# Dual_Motor_Driver.net
KiCad netlist of a schematic drawn in EAGLE
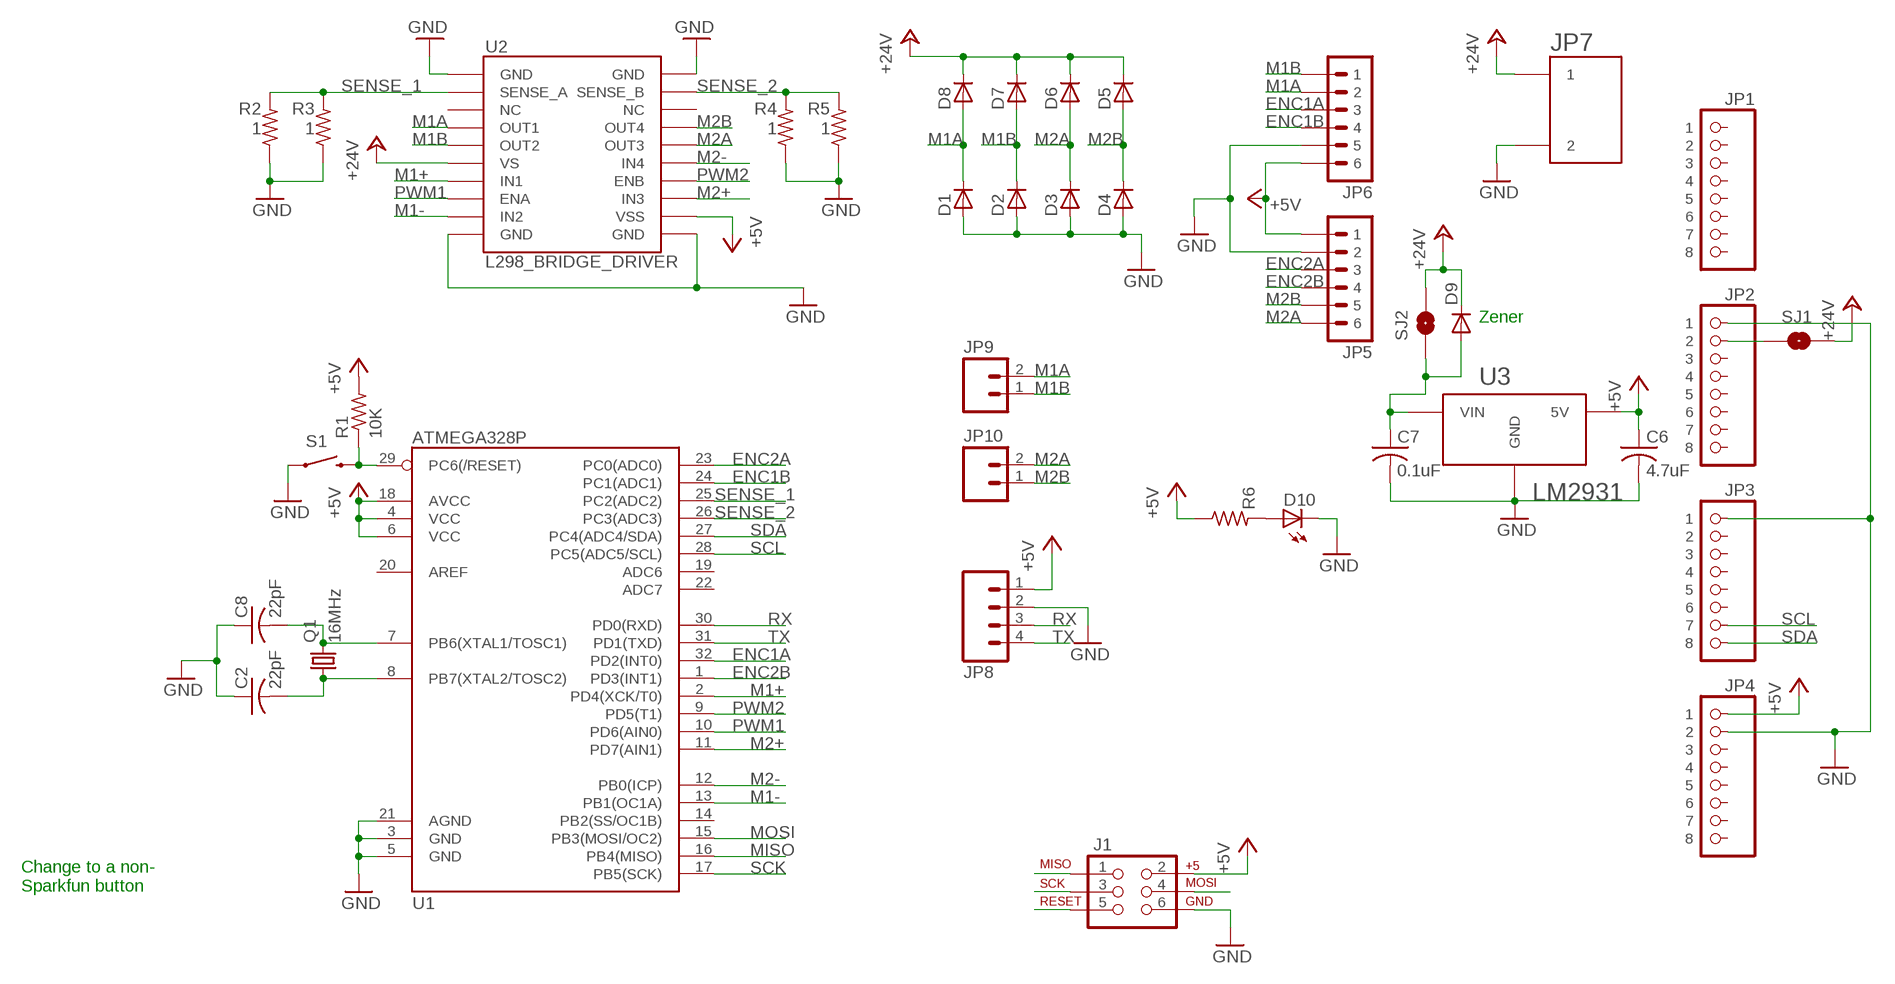
[diagram p0: schematic, sheet 1]

(export (version "E")
  (design (tool "Eeschema 10.0.6"))
  (components
    (comp (ref "C2")
      (value "22pF")
      (footprint "eagle-import:C0603")
      (libsource (lib "eagle-import") (part "C-USC0603"))
    )
    (comp (ref "C6")
      (value "4.7uF")
      (footprint "eagle-import:C0603")
      (libsource (lib "eagle-import") (part "C-USC0603"))
    )
    (comp (ref "C7")
      (value "0.1uF")
      (footprint "eagle-import:C0603")
      (libsource (lib "eagle-import") (part "C-USC0603"))
    )
    (comp (ref "C8")
      (value "22pF")
      (footprint "eagle-import:C0603")
      (libsource (lib "eagle-import") (part "C-USC0603"))
    )
    (comp (ref "D1")
      (value "D-SOD123")
      (footprint "eagle-import:SOD123")
      (fields (field (name "PART#") "CDBW140-G"))
      (libsource (lib "eagle-import") (part "D-SOD123"))
    )
    (comp (ref "D2")
      (value "D-SOD123")
      (footprint "eagle-import:SOD123")
      (fields (field (name "PART#") "CDBW140-G"))
      (libsource (lib "eagle-import") (part "D-SOD123"))
    )
    (comp (ref "D3")
      (value "D-SOD123")
      (footprint "eagle-import:SOD123")
      (fields (field (name "PART#") "CDBW140-G"))
      (libsource (lib "eagle-import") (part "D-SOD123"))
    )
    (comp (ref "D4")
      (value "D-SOD123")
      (footprint "eagle-import:SOD123")
      (fields (field (name "PART#") "CDBW140-G"))
      (libsource (lib "eagle-import") (part "D-SOD123"))
    )
    (comp (ref "D5")
      (value "D-SOD123")
      (footprint "eagle-import:SOD123")
      (fields (field (name "PART#") "CDBW140-G"))
      (libsource (lib "eagle-import") (part "D-SOD123"))
    )
    (comp (ref "D6")
      (value "D-SOD123")
      (footprint "eagle-import:SOD123")
      (fields (field (name "PART#") "CDBW140-G"))
      (libsource (lib "eagle-import") (part "D-SOD123"))
    )
    (comp (ref "D7")
      (value "D-SOD123")
      (footprint "eagle-import:SOD123")
      (fields (field (name "PART#") "CDBW140-G"))
      (libsource (lib "eagle-import") (part "D-SOD123"))
    )
    (comp (ref "D8")
      (value "D-SOD123")
      (footprint "eagle-import:SOD123")
      (fields (field (name "PART#") "CDBW140-G"))
      (libsource (lib "eagle-import") (part "D-SOD123"))
    )
    (comp (ref "D9")
      (value "DIODE-DO214AA")
      (footprint "eagle-import:DO214AA")
      (libsource (lib "eagle-import") (part "DIODE-DO214AA"))
    )
    (comp (ref "D10")
      (value "LED-GREENLED-0805_NO_SILK")
      (footprint "eagle-import:LED-0805")
      (libsource (lib "eagle-import") (part "LED-GREENLED-0805_NO_SILK"))
    )
    (comp (ref "J1")
      (value "AVR_SPI_PRG_62X3_LOCK")
      (footprint "eagle-import:2X3_LOCK")
      (libsource (lib "eagle-import") (part "AVR_SPI_PRG_62X3_LOCK"))
    )
    (comp (ref "JP1")
      (value "8-PIN_HEADER")
      (footprint "eagle-import:8-PIN_RECEPTACLE_LOCK_NO-SS")
      (libsource (lib "eagle-import") (part "8-PIN_HEADER"))
    )
    (comp (ref "JP2")
      (value "8-PIN_HEADER")
      (footprint "eagle-import:8-PIN_RECEPTACLE_LOCK_NO-SS")
      (libsource (lib "eagle-import") (part "8-PIN_HEADER"))
    )
    (comp (ref "JP3")
      (value "8-PIN_HEADER")
      (footprint "eagle-import:8-PIN_RECEPTACLE_LOCK_NO-SS")
      (libsource (lib "eagle-import") (part "8-PIN_HEADER"))
    )
    (comp (ref "JP4")
      (value "8-PIN_HEADER")
      (footprint "eagle-import:8-PIN_RECEPTACLE_LOCK_NO-SS")
      (libsource (lib "eagle-import") (part "8-PIN_HEADER"))
    )
    (comp (ref "JP5")
      (value "6PIN-SH_RIGHT_ANGLE")
      (footprint "eagle-import:6PIN-SH_SERIES_RA")
      (fields (field (name "PART#") "SM06B-SRSS-TB(LF)(SN)"))
      (libsource (lib "eagle-import") (part "6PIN-SH_RIGHT_ANGLE"))
    )
    (comp (ref "JP6")
      (value "6PIN-SH_RIGHT_ANGLE")
      (footprint "eagle-import:6PIN-SH_SERIES_RA")
      (fields (field (name "PART#") "SM06B-SRSS-TB(LF)(SN)"))
      (libsource (lib "eagle-import") (part "6PIN-SH_RIGHT_ANGLE"))
    )
    (comp (ref "JP7")
      (value "2-POS_SMD_TERM_BLOCK")
      (footprint "eagle-import:2-POS_SMD_TERMINAL_BLOCK")
      (libsource (lib "eagle-import") (part "2-POS_SMD_TERM_BLOCK"))
    )
    (comp (ref "JP8")
      (value "M04LOCK")
      (footprint "eagle-import:1X04_LOCK")
      (libsource (lib "eagle-import") (part "M04LOCK"))
    )
    (comp (ref "JP9")
      (value "M02PTH")
      (footprint "eagle-import:1X02")
      (libsource (lib "eagle-import") (part "M02PTH"))
    )
    (comp (ref "JP10")
      (value "M02PTH")
      (footprint "eagle-import:1X02")
      (libsource (lib "eagle-import") (part "M02PTH"))
    )
    (comp (ref "Q1")
      (value "16MHz")
      (footprint "eagle-import:CTS406")
      (fields (field (name "PART#") "406C35D16M00000"))
      (libsource (lib "eagle-import") (part "CRYSTALCTS406"))
    )
    (comp (ref "R1")
      (value "10K")
      (footprint "eagle-import:R0603")
      (libsource (lib "eagle-import") (part "R-US_R0603"))
    )
    (comp (ref "R2")
      (value "1")
      (footprint "eagle-import:R0603")
      (libsource (lib "eagle-import") (part "R-US_R0603"))
    )
    (comp (ref "R3")
      (value "1")
      (footprint "eagle-import:R0603")
      (libsource (lib "eagle-import") (part "R-US_R0603"))
    )
    (comp (ref "R4")
      (value "1")
      (footprint "eagle-import:R0603")
      (libsource (lib "eagle-import") (part "R-US_R0603"))
    )
    (comp (ref "R5")
      (value "1")
      (footprint "eagle-import:R0603")
      (libsource (lib "eagle-import") (part "R-US_R0603"))
    )
    (comp (ref "R6")
      (value "R-US_R0603")
      (footprint "eagle-import:R0603")
      (libsource (lib "eagle-import") (part "R-US_R0603"))
    )
    (comp (ref "S1")
      (value "SWITCH-MOMENTARY-2SMD")
      (footprint "eagle-import:TACTILE_SWITCH_SMD")
      (libsource (lib "eagle-import") (part "SWITCH-MOMENTARY-2SMD"))
    )
    (comp (ref "SJ1")
      (value "SOLDERJUMPERNC")
      (footprint "eagle-import:SJ_2S")
      (libsource (lib "eagle-import") (part "SOLDERJUMPERNC"))
    )
    (comp (ref "SJ2")
      (value "SOLDERJUMPERTRACE")
      (footprint "eagle-import:SJ_2S-TRACE")
      (libsource (lib "eagle-import") (part "SOLDERJUMPERTRACE"))
    )
    (comp (ref "U1")
      (value "ATMEGA328P")
      (footprint "eagle-import:TQFP32-08")
      (libsource (lib "eagle-import") (part "ATMEGA328_SMT"))
    )
    (comp (ref "U2")
      (value "L298_BRIDGE_DRIVER")
      (footprint "eagle-import:POWERSO20")
      (libsource (lib "eagle-import") (part "L298_BRIDGE_DRIVER"))
    )
    (comp (ref "U3")
      (value "LM2931")
      (footprint "eagle-import:TO263")
      (libsource (lib "eagle-import") (part "LM2931"))
    )
  )
  (nets
    (net (code "1") (name "+5V") (class "Default")
      (node (ref "C6") (pin "1") (pinfunction "1_1") (pintype "passive"))
      (node (ref "J1") (pin "2") (pinfunction "2_2") (pintype "passive"))
      (node (ref "JP4") (pin "P$1") (pinfunction "1_P$1") (pintype "passive"))
      (node (ref "JP5") (pin "P$1") (pinfunction "1_P$1") (pintype "passive"))
      (node (ref "JP6") (pin "P$6") (pinfunction "6_P$6") (pintype "passive"))
      (node (ref "JP8") (pin "1") (pinfunction "1_1") (pintype "passive"))
      (node (ref "R1") (pin "2") (pinfunction "2_2") (pintype "passive"))
      (node (ref "R6") (pin "1") (pinfunction "1_1") (pintype "passive"))
      (node (ref "U1") (pin "18") (pinfunction "AVCC_18") (pintype "bidirectional"))
      (node (ref "U1") (pin "4") (pinfunction "VCC_4") (pintype "bidirectional"))
      (node (ref "U1") (pin "6") (pinfunction "VCC_6") (pintype "bidirectional"))
      (node (ref "U2") (pin "12") (pinfunction "VSS_12") (pintype "bidirectional"))
      (node (ref "U3") (pin "P$3") (pinfunction "5V_P$3") (pintype "bidirectional"))
    )
    (net (code "2") (name "+24V") (class "Default")
      (node (ref "D5") (pin "1") (pinfunction "C_1") (pintype "passive"))
      (node (ref "D6") (pin "1") (pinfunction "C_1") (pintype "passive"))
      (node (ref "D7") (pin "1") (pinfunction "C_1") (pintype "passive"))
      (node (ref "D8") (pin "1") (pinfunction "C_1") (pintype "passive"))
      (node (ref "D9") (pin "C") (pinfunction "C_C") (pintype "passive"))
      (node (ref "JP7") (pin "P$3") (pinfunction "1_P$3") (pintype "bidirectional"))
      (node (ref "SJ1") (pin "2") (pinfunction "2_2") (pintype "passive"))
      (node (ref "SJ2") (pin "2") (pinfunction "2_2") (pintype "passive"))
      (node (ref "U2") (pin "6") (pinfunction "VS_6") (pintype "bidirectional"))
    )
    (net (code "3") (name "/ENC1A") (class "Default")
      (node (ref "JP6") (pin "P$3") (pinfunction "3_P$3") (pintype "passive"))
      (node (ref "U1") (pin "32") (pinfunction "PD2(INT0)_32") (pintype "bidirectional"))
    )
    (net (code "4") (name "/ENC1B") (class "Default")
      (node (ref "JP6") (pin "P$4") (pinfunction "4_P$4") (pintype "passive"))
      (node (ref "U1") (pin "24") (pinfunction "PC1(ADC1)_24") (pintype "bidirectional"))
    )
    (net (code "5") (name "/ENC2A") (class "Default")
      (node (ref "JP5") (pin "P$3") (pinfunction "3_P$3") (pintype "passive"))
      (node (ref "U1") (pin "23") (pinfunction "PC0(ADC0)_23") (pintype "bidirectional"))
    )
    (net (code "6") (name "/ENC2B") (class "Default")
      (node (ref "JP5") (pin "P$4") (pinfunction "4_P$4") (pintype "passive"))
      (node (ref "U1") (pin "1") (pinfunction "PD3(INT1)_1") (pintype "bidirectional"))
    )
    (net (code "7") (name "/M1+") (class "Default")
      (node (ref "U1") (pin "2") (pinfunction "PD4(XCK/T0)_2") (pintype "bidirectional"))
      (node (ref "U2") (pin "7") (pinfunction "IN1_7") (pintype "bidirectional"))
    )
    (net (code "8") (name "/M1-") (class "Default")
      (node (ref "U1") (pin "13") (pinfunction "PB1(OC1A)_13") (pintype "bidirectional"))
      (node (ref "U2") (pin "9") (pinfunction "IN2_9") (pintype "bidirectional"))
    )
    (net (code "9") (name "/M1A") (class "Default")
      (node (ref "D1") (pin "1") (pinfunction "C_1") (pintype "passive"))
      (node (ref "D8") (pin "2") (pinfunction "A_2") (pintype "passive"))
      (node (ref "JP6") (pin "P$2") (pinfunction "2_P$2") (pintype "passive"))
      (node (ref "JP9") (pin "2") (pinfunction "2_2") (pintype "passive"))
      (node (ref "U2") (pin "4") (pinfunction "OUT1_4") (pintype "bidirectional"))
    )
    (net (code "10") (name "/M1B") (class "Default")
      (node (ref "D2") (pin "1") (pinfunction "C_1") (pintype "passive"))
      (node (ref "D7") (pin "2") (pinfunction "A_2") (pintype "passive"))
      (node (ref "JP6") (pin "P$1") (pinfunction "1_P$1") (pintype "passive"))
      (node (ref "JP9") (pin "1") (pinfunction "1_1") (pintype "passive"))
      (node (ref "U2") (pin "5") (pinfunction "OUT2_5") (pintype "bidirectional"))
    )
    (net (code "11") (name "/M2+") (class "Default")
      (node (ref "U1") (pin "11") (pinfunction "PD7(AIN1)_11") (pintype "bidirectional"))
      (node (ref "U2") (pin "13") (pinfunction "IN3_13") (pintype "bidirectional"))
    )
    (net (code "12") (name "/M2-") (class "Default")
      (node (ref "U1") (pin "12") (pinfunction "PB0(ICP)_12") (pintype "bidirectional"))
      (node (ref "U2") (pin "15") (pinfunction "IN4_15") (pintype "bidirectional"))
    )
    (net (code "13") (name "/M2A") (class "Default")
      (node (ref "D3") (pin "1") (pinfunction "C_1") (pintype "passive"))
      (node (ref "D6") (pin "2") (pinfunction "A_2") (pintype "passive"))
      (node (ref "JP10") (pin "2") (pinfunction "2_2") (pintype "passive"))
      (node (ref "JP5") (pin "P$6") (pinfunction "6_P$6") (pintype "passive"))
      (node (ref "U2") (pin "16") (pinfunction "OUT3_16") (pintype "bidirectional"))
    )
    (net (code "14") (name "/M2B") (class "Default")
      (node (ref "D4") (pin "1") (pinfunction "C_1") (pintype "passive"))
      (node (ref "D5") (pin "2") (pinfunction "A_2") (pintype "passive"))
      (node (ref "JP10") (pin "1") (pinfunction "1_1") (pintype "passive"))
      (node (ref "JP5") (pin "P$5") (pinfunction "5_P$5") (pintype "passive"))
      (node (ref "U2") (pin "17") (pinfunction "OUT4_17") (pintype "bidirectional"))
    )
    (net (code "15") (name "/MISO") (class "Default")
      (node (ref "J1") (pin "1") (pinfunction "1_1") (pintype "passive"))
      (node (ref "U1") (pin "16") (pinfunction "PB4(MISO)_16") (pintype "bidirectional"))
    )
    (net (code "16") (name "/MOSI") (class "Default")
      (node (ref "J1") (pin "4") (pinfunction "4_4") (pintype "passive"))
      (node (ref "U1") (pin "15") (pinfunction "PB3(MOSI/OC2)_15") (pintype "bidirectional"))
    )
    (net (code "17") (name "/PWM1") (class "Default")
      (node (ref "U1") (pin "10") (pinfunction "PD6(AIN0)_10") (pintype "bidirectional"))
      (node (ref "U2") (pin "8") (pinfunction "ENA_8") (pintype "bidirectional"))
    )
    (net (code "18") (name "/PWM2") (class "Default")
      (node (ref "U1") (pin "9") (pinfunction "PD5(T1)_9") (pintype "bidirectional"))
      (node (ref "U2") (pin "14") (pinfunction "ENB_14") (pintype "bidirectional"))
    )
    (net (code "19") (name "/RESET") (class "Default")
      (node (ref "J1") (pin "5") (pinfunction "5_5") (pintype "passive"))
      (node (ref "R1") (pin "1") (pinfunction "1_1") (pintype "passive"))
      (node (ref "S1") (pin "3") (pinfunction "2_3") (pintype "passive"))
      (node (ref "U1") (pin "29") (pinfunction "PC6(/RESET)_29") (pintype "bidirectional"))
    )
    (net (code "20") (name "/RX") (class "Default")
      (node (ref "JP8") (pin "3") (pinfunction "3_3") (pintype "passive"))
      (node (ref "U1") (pin "30") (pinfunction "PD0(RXD)_30") (pintype "bidirectional"))
    )
    (net (code "21") (name "/SCK") (class "Default")
      (node (ref "J1") (pin "3") (pinfunction "3_3") (pintype "passive"))
      (node (ref "U1") (pin "17") (pinfunction "PB5(SCK)_17") (pintype "bidirectional"))
    )
    (net (code "22") (name "/SCL") (class "Default")
      (node (ref "JP3") (pin "P$7") (pinfunction "7_P$7") (pintype "passive"))
      (node (ref "U1") (pin "28") (pinfunction "PC5(ADC5/SCL)_28") (pintype "bidirectional"))
    )
    (net (code "23") (name "/SDA") (class "Default")
      (node (ref "JP3") (pin "P$8") (pinfunction "8_P$8") (pintype "passive"))
      (node (ref "U1") (pin "27") (pinfunction "PC4(ADC4/SDA)_27") (pintype "bidirectional"))
    )
    (net (code "24") (name "/SENSE_1") (class "Default")
      (node (ref "R2") (pin "2") (pinfunction "2_2") (pintype "passive"))
      (node (ref "R3") (pin "2") (pinfunction "2_2") (pintype "passive"))
      (node (ref "U1") (pin "25") (pinfunction "PC2(ADC2)_25") (pintype "bidirectional"))
      (node (ref "U2") (pin "2") (pinfunction "SENSE_A_2") (pintype "bidirectional"))
    )
    (net (code "25") (name "/SENSE_2") (class "Default")
      (node (ref "R4") (pin "2") (pinfunction "2_2") (pintype "passive"))
      (node (ref "R5") (pin "2") (pinfunction "2_2") (pintype "passive"))
      (node (ref "U1") (pin "26") (pinfunction "PC3(ADC3)_26") (pintype "bidirectional"))
      (node (ref "U2") (pin "19") (pinfunction "SENSE_B_19") (pintype "bidirectional"))
    )
    (net (code "26") (name "/TX") (class "Default")
      (node (ref "JP8") (pin "4") (pinfunction "4_4") (pintype "passive"))
      (node (ref "U1") (pin "31") (pinfunction "PD1(TXD)_31") (pintype "bidirectional"))
    )
    (net (code "27") (name "GND") (class "Default")
      (node (ref "C2") (pin "1") (pinfunction "1_1") (pintype "passive"))
      (node (ref "C6") (pin "2") (pinfunction "2_2") (pintype "passive"))
      (node (ref "C7") (pin "2") (pinfunction "2_2") (pintype "passive"))
      (node (ref "C8") (pin "1") (pinfunction "1_1") (pintype "passive"))
      (node (ref "D1") (pin "2") (pinfunction "A_2") (pintype "passive"))
      (node (ref "D10") (pin "2") (pinfunction "C_2") (pintype "passive"))
      (node (ref "D2") (pin "2") (pinfunction "A_2") (pintype "passive"))
      (node (ref "D3") (pin "2") (pinfunction "A_2") (pintype "passive"))
      (node (ref "D4") (pin "2") (pinfunction "A_2") (pintype "passive"))
      (node (ref "J1") (pin "6") (pinfunction "6_6") (pintype "passive"))
      (node (ref "JP2") (pin "P$1") (pinfunction "1_P$1") (pintype "passive"))
      (node (ref "JP3") (pin "P$1") (pinfunction "1_P$1") (pintype "passive"))
      (node (ref "JP4") (pin "P$2") (pinfunction "2_P$2") (pintype "passive"))
      (node (ref "JP5") (pin "P$2") (pinfunction "2_P$2") (pintype "passive"))
      (node (ref "JP6") (pin "P$5") (pinfunction "5_P$5") (pintype "passive"))
      (node (ref "JP7") (pin "P$4") (pinfunction "2_P$4") (pintype "bidirectional"))
      (node (ref "JP8") (pin "2") (pinfunction "2_2") (pintype "passive"))
      (node (ref "R2") (pin "1") (pinfunction "1_1") (pintype "passive"))
      (node (ref "R3") (pin "1") (pinfunction "1_1") (pintype "passive"))
      (node (ref "R4") (pin "1") (pinfunction "1_1") (pintype "passive"))
      (node (ref "R5") (pin "1") (pinfunction "1_1") (pintype "passive"))
      (node (ref "S1") (pin "1") (pinfunction "1_1") (pintype "passive"))
      (node (ref "U1") (pin "21") (pinfunction "AGND_21") (pintype "bidirectional"))
      (node (ref "U1") (pin "3") (pinfunction "GND_3") (pintype "bidirectional"))
      (node (ref "U1") (pin "5") (pinfunction "GND_5") (pintype "bidirectional"))
      (node (ref "U2") (pin "1") (pinfunction "GND_1") (pintype "bidirectional"))
      (node (ref "U2") (pin "10") (pinfunction "GND_10") (pintype "bidirectional"))
      (node (ref "U2") (pin "11") (pinfunction "GND_11") (pintype "bidirectional"))
      (node (ref "U2") (pin "20") (pinfunction "GND_20") (pintype "bidirectional"))
      (node (ref "U3") (pin "P$1") (pinfunction "GND_P$1") (pintype "bidirectional"))
    )
    (net (code "28") (name "Net-(D10-A)") (class "Default")
      (node (ref "D10") (pin "1") (pinfunction "A_1") (pintype "passive"))
      (node (ref "R6") (pin "2") (pinfunction "2_2") (pintype "passive"))
    )
    (net (code "29") (name "Net-(JP2-2)") (class "Default")
      (node (ref "JP2") (pin "P$2") (pinfunction "2_P$2") (pintype "passive"))
      (node (ref "SJ1") (pin "1") (pinfunction "1_1") (pintype "passive"))
    )
    (net (code "30") (name "Net-(Q1-2)") (class "Default")
      (node (ref "C8") (pin "2") (pinfunction "2_2") (pintype "passive"))
      (node (ref "Q1") (pin "3") (pinfunction "2_3") (pintype "passive"))
      (node (ref "U1") (pin "7") (pinfunction "PB6(XTAL1/TOSC1)_7") (pintype "bidirectional"))
    )
    (net (code "31") (name "Net-(U1-PB7(XTAL2{slash}TOSC2))") (class "Default")
      (node (ref "C2") (pin "2") (pinfunction "2_2") (pintype "passive"))
      (node (ref "Q1") (pin "1") (pinfunction "1_1") (pintype "passive"))
      (node (ref "U1") (pin "8") (pinfunction "PB7(XTAL2/TOSC2)_8") (pintype "bidirectional"))
    )
    (net (code "32") (name "Net-(U3-VIN)") (class "Default")
      (node (ref "C7") (pin "1") (pinfunction "1_1") (pintype "passive"))
      (node (ref "D9") (pin "A") (pinfunction "A_A") (pintype "passive"))
      (node (ref "SJ2") (pin "1") (pinfunction "1_1") (pintype "passive"))
      (node (ref "U3") (pin "P$2") (pinfunction "VIN_P$2") (pintype "bidirectional"))
    )
    (net (code "33") (name "unconnected-(JP1-1-PadP$1)") (class "Default")
      (node (ref "JP1") (pin "P$1") (pinfunction "1_P$1") (pintype "passive"))
    )
    (net (code "34") (name "unconnected-(JP1-2-PadP$2)") (class "Default")
      (node (ref "JP1") (pin "P$2") (pinfunction "2_P$2") (pintype "passive"))
    )
    (net (code "35") (name "unconnected-(JP1-3-PadP$3)") (class "Default")
      (node (ref "JP1") (pin "P$3") (pinfunction "3_P$3") (pintype "passive"))
    )
    (net (code "36") (name "unconnected-(JP1-4-PadP$4)") (class "Default")
      (node (ref "JP1") (pin "P$4") (pinfunction "4_P$4") (pintype "passive"))
    )
    (net (code "37") (name "unconnected-(JP1-5-PadP$5)") (class "Default")
      (node (ref "JP1") (pin "P$5") (pinfunction "5_P$5") (pintype "passive"))
    )
    (net (code "38") (name "unconnected-(JP1-6-PadP$6)") (class "Default")
      (node (ref "JP1") (pin "P$6") (pinfunction "6_P$6") (pintype "passive"))
    )
    (net (code "39") (name "unconnected-(JP1-7-PadP$7)") (class "Default")
      (node (ref "JP1") (pin "P$7") (pinfunction "7_P$7") (pintype "passive"))
    )
    (net (code "40") (name "unconnected-(JP1-8-PadP$8)") (class "Default")
      (node (ref "JP1") (pin "P$8") (pinfunction "8_P$8") (pintype "passive"))
    )
    (net (code "41") (name "unconnected-(JP2-3-PadP$3)") (class "Default")
      (node (ref "JP2") (pin "P$3") (pinfunction "3_P$3") (pintype "passive"))
    )
    (net (code "42") (name "unconnected-(JP2-4-PadP$4)") (class "Default")
      (node (ref "JP2") (pin "P$4") (pinfunction "4_P$4") (pintype "passive"))
    )
    (net (code "43") (name "unconnected-(JP2-5-PadP$5)") (class "Default")
      (node (ref "JP2") (pin "P$5") (pinfunction "5_P$5") (pintype "passive"))
    )
    (net (code "44") (name "unconnected-(JP2-6-PadP$6)") (class "Default")
      (node (ref "JP2") (pin "P$6") (pinfunction "6_P$6") (pintype "passive"))
    )
    (net (code "45") (name "unconnected-(JP2-7-PadP$7)") (class "Default")
      (node (ref "JP2") (pin "P$7") (pinfunction "7_P$7") (pintype "passive"))
    )
    (net (code "46") (name "unconnected-(JP2-8-PadP$8)") (class "Default")
      (node (ref "JP2") (pin "P$8") (pinfunction "8_P$8") (pintype "passive"))
    )
    (net (code "47") (name "unconnected-(JP3-2-PadP$2)") (class "Default")
      (node (ref "JP3") (pin "P$2") (pinfunction "2_P$2") (pintype "passive"))
    )
    (net (code "48") (name "unconnected-(JP3-3-PadP$3)") (class "Default")
      (node (ref "JP3") (pin "P$3") (pinfunction "3_P$3") (pintype "passive"))
    )
    (net (code "49") (name "unconnected-(JP3-4-PadP$4)") (class "Default")
      (node (ref "JP3") (pin "P$4") (pinfunction "4_P$4") (pintype "passive"))
    )
    (net (code "50") (name "unconnected-(JP3-5-PadP$5)") (class "Default")
      (node (ref "JP3") (pin "P$5") (pinfunction "5_P$5") (pintype "passive"))
    )
    (net (code "51") (name "unconnected-(JP3-6-PadP$6)") (class "Default")
      (node (ref "JP3") (pin "P$6") (pinfunction "6_P$6") (pintype "passive"))
    )
    (net (code "52") (name "unconnected-(JP4-3-PadP$3)") (class "Default")
      (node (ref "JP4") (pin "P$3") (pinfunction "3_P$3") (pintype "passive"))
    )
    (net (code "53") (name "unconnected-(JP4-4-PadP$4)") (class "Default")
      (node (ref "JP4") (pin "P$4") (pinfunction "4_P$4") (pintype "passive"))
    )
    (net (code "54") (name "unconnected-(JP4-5-PadP$5)") (class "Default")
      (node (ref "JP4") (pin "P$5") (pinfunction "5_P$5") (pintype "passive"))
    )
    (net (code "55") (name "unconnected-(JP4-6-PadP$6)") (class "Default")
      (node (ref "JP4") (pin "P$6") (pinfunction "6_P$6") (pintype "passive"))
    )
    (net (code "56") (name "unconnected-(JP4-7-PadP$7)") (class "Default")
      (node (ref "JP4") (pin "P$7") (pinfunction "7_P$7") (pintype "passive"))
    )
    (net (code "57") (name "unconnected-(JP4-8-PadP$8)") (class "Default")
      (node (ref "JP4") (pin "P$8") (pinfunction "8_P$8") (pintype "passive"))
    )
    (net (code "58") (name "unconnected-(U1-ADC6-Pad19)") (class "Default")
      (node (ref "U1") (pin "19") (pinfunction "ADC6_19") (pintype "bidirectional"))
    )
    (net (code "59") (name "unconnected-(U1-ADC7-Pad22)") (class "Default")
      (node (ref "U1") (pin "22") (pinfunction "ADC7_22") (pintype "bidirectional"))
    )
    (net (code "60") (name "unconnected-(U1-AREF-Pad20)") (class "Default")
      (node (ref "U1") (pin "20") (pinfunction "AREF_20") (pintype "bidirectional"))
    )
    (net (code "61") (name "unconnected-(U1-PB2(SS{slash}OC1B)-Pad14)") (class "Default")
      (node (ref "U1") (pin "14") (pinfunction "PB2(SS/OC1B)_14") (pintype "bidirectional"))
    )
    (net (code "62") (name "unconnected-(U2-NC-Pad3)") (class "Default")
      (node (ref "U2") (pin "3") (pinfunction "NC_3") (pintype "bidirectional"))
    )
    (net (code "63") (name "unconnected-(U2-NC-Pad18)") (class "Default")
      (node (ref "U2") (pin "18") (pinfunction "NC_18") (pintype "bidirectional"))
    )
  )
)
